# eggbotD1.net
KiCad netlist of a schematic drawn in EAGLE
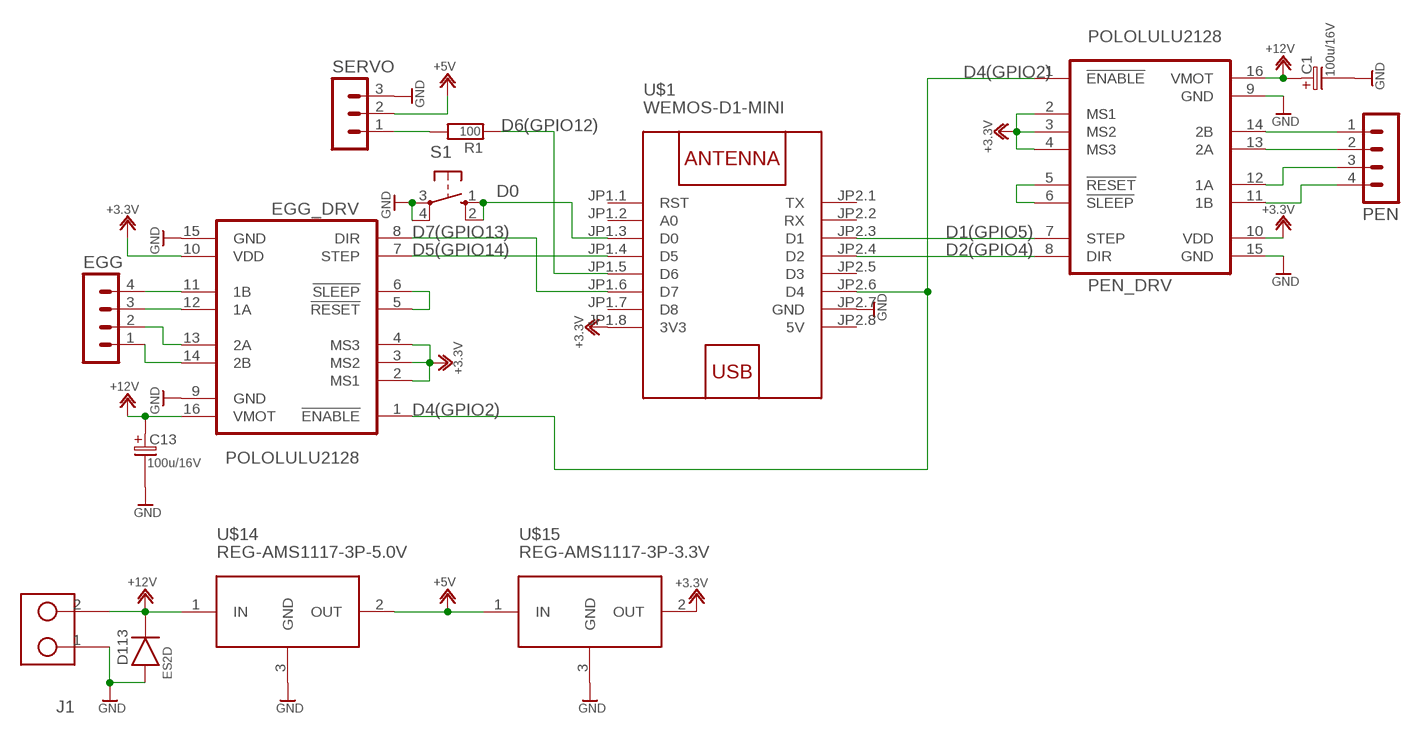
[diagram p0: schematic, sheet 1]

(export (version "E")
  (design (tool "Eeschema 10.0.6"))
  (components
    (comp (ref "C1")
      (value "100u/16V")
      (footprint "eagle-import:ES-3,5_8")
      (libsource (lib "eagle-import") (part "C-EL-3,5/8"))
    )
    (comp (ref "C13")
      (value "100u/16V")
      (footprint "eagle-import:ES-3,5_8")
      (libsource (lib "eagle-import") (part "C-EL-3,5/8"))
    )
    (comp (ref "D113")
      (value "ES2D")
      (footprint "eagle-import:SMB")
      (libsource (lib "eagle-import") (part "DIODESMB"))
    )
    (comp (ref "EGG")
      (value "MA04-1")
      (footprint "eagle-import:MA04-1")
      (libsource (lib "eagle-import") (part "MA04-1"))
    )
    (comp (ref "EGG_DRV")
      (value "POLOLULU2128")
      (footprint "eagle-import:POLOLULU2128")
      (libsource (lib "eagle-import") (part "POLOLULU2128"))
    )
    (comp (ref "J1")
      (value "GMKDS-2")
      (footprint "eagle-import:GMKDS1,5")
      (libsource (lib "eagle-import") (part "GMKDS-2"))
    )
    (comp (ref "PEN")
      (value "MA04-1")
      (footprint "eagle-import:MA04-1")
      (libsource (lib "eagle-import") (part "MA04-1"))
    )
    (comp (ref "PEN_DRV")
      (value "POLOLULU2128")
      (footprint "eagle-import:POLOLULU2128")
      (libsource (lib "eagle-import") (part "POLOLULU2128"))
    )
    (comp (ref "R1")
      (value "100")
      (footprint "eagle-import:0805")
      (libsource (lib "eagle-import") (part "RES-0805"))
    )
    (comp (ref "S1")
      (value "10-XX")
      (footprint "eagle-import:B3F-10XX")
      (fields (field (name "MPN") "B3F-1000"))
      (libsource (lib "eagle-import") (part "10-XX"))
    )
    (comp (ref "SERVO")
      (value "MA03-1")
      (footprint "eagle-import:MA03-1")
      (libsource (lib "eagle-import") (part "MA03-1"))
    )
    (comp (ref "U$1")
      (value "WEMOS-D1-MINI")
      (footprint "eagle-import:WEMOS-D1-MINI")
      (libsource (lib "eagle-import") (part "WEMOS-D1-MINI"))
    )
    (comp (ref "U$14")
      (value "REG-AMS1117-3P-5.0V")
      (footprint "eagle-import:REG-AMS1117-3P")
      (libsource (lib "eagle-import") (part "REG-AMS1117-3P-5.0V"))
    )
    (comp (ref "U$15")
      (value "REG-AMS1117-3P-3.3V")
      (footprint "eagle-import:REG-AMS1117-3P")
      (libsource (lib "eagle-import") (part "REG-AMS1117-3P-3.3V"))
    )
  )
  (nets
    (net (code "1") (name "+3.3V") (class "Default")
      (node (ref "EGG_DRV") (pin "10") (pinfunction "VDD_10") (pintype "power_in"))
      (node (ref "EGG_DRV") (pin "2") (pinfunction "MS1_2") (pintype "input"))
      (node (ref "EGG_DRV") (pin "3") (pinfunction "MS2_3") (pintype "input"))
      (node (ref "EGG_DRV") (pin "4") (pinfunction "MS3_4") (pintype "input"))
      (node (ref "PEN_DRV") (pin "10") (pinfunction "VDD_10") (pintype "power_in"))
      (node (ref "PEN_DRV") (pin "2") (pinfunction "MS1_2") (pintype "input"))
      (node (ref "PEN_DRV") (pin "3") (pinfunction "MS2_3") (pintype "input"))
      (node (ref "PEN_DRV") (pin "4") (pinfunction "MS3_4") (pintype "input"))
      (node (ref "U$1") (pin "JP1.8") (pinfunction "3V3_JP1.8") (pintype "power_in"))
      (node (ref "U$15") (pin "2") (pinfunction "OUT_2") (pintype "bidirectional"))
    )
    (net (code "2") (name "+5V") (class "Default")
      (node (ref "SERVO") (pin "2") (pinfunction "2_2") (pintype "passive"))
      (node (ref "U$14") (pin "2") (pinfunction "OUT_2") (pintype "bidirectional"))
      (node (ref "U$15") (pin "1") (pinfunction "IN_1") (pintype "bidirectional"))
    )
    (net (code "3") (name "+12V") (class "Default")
      (node (ref "C1") (pin "1") (pinfunction "1_1") (pintype "passive"))
      (node (ref "C13") (pin "1") (pinfunction "1_1") (pintype "passive"))
      (node (ref "D113") (pin "2") (pinfunction "K_2") (pintype "passive"))
      (node (ref "EGG_DRV") (pin "16") (pinfunction "VMOT_16") (pintype "power_in"))
      (node (ref "J1") (pin "2") (pinfunction "2_2") (pintype "passive"))
      (node (ref "PEN_DRV") (pin "16") (pinfunction "VMOT_16") (pintype "power_in"))
      (node (ref "U$14") (pin "1") (pinfunction "IN_1") (pintype "bidirectional"))
    )
    (net (code "4") (name "/5V") (class "Default")
      (node (ref "U$1") (pin "JP2.8") (pinfunction "5V_JP2.8") (pintype "power_in"))
    )
    (net (code "5") (name "/D0") (class "Default")
      (node (ref "S1") (pin "1") (pinfunction "S_1") (pintype "passive"))
      (node (ref "S1") (pin "2") (pinfunction "S1_2") (pintype "passive"))
      (node (ref "U$1") (pin "JP1.3") (pinfunction "D0_JP1.3") (pintype "bidirectional"))
    )
    (net (code "6") (name "/D1(GPIO5)") (class "Default")
      (node (ref "PEN_DRV") (pin "7") (pinfunction "STEP_7") (pintype "input"))
      (node (ref "U$1") (pin "JP2.3") (pinfunction "D1_JP2.3") (pintype "bidirectional"))
    )
    (net (code "7") (name "/D2(GPIO4)") (class "Default")
      (node (ref "PEN_DRV") (pin "8") (pinfunction "DIR_8") (pintype "input"))
      (node (ref "U$1") (pin "JP2.4") (pinfunction "D2_JP2.4") (pintype "bidirectional"))
    )
    (net (code "8") (name "/D4(GPIO2)") (class "Default")
      (node (ref "EGG_DRV") (pin "1") (pinfunction "~{ENABLE}_1") (pintype "input"))
      (node (ref "PEN_DRV") (pin "1") (pinfunction "~{ENABLE}_1") (pintype "input"))
      (node (ref "U$1") (pin "JP2.6") (pinfunction "D4_JP2.6") (pintype "bidirectional"))
    )
    (net (code "9") (name "/D5(GPIO14)") (class "Default")
      (node (ref "EGG_DRV") (pin "7") (pinfunction "STEP_7") (pintype "input"))
      (node (ref "U$1") (pin "JP1.4") (pinfunction "D5_JP1.4") (pintype "bidirectional"))
    )
    (net (code "10") (name "/D6(GPIO12)") (class "Default")
      (node (ref "R1") (pin "1") (pinfunction "1_1") (pintype "passive"))
      (node (ref "U$1") (pin "JP1.5") (pinfunction "D6_JP1.5") (pintype "bidirectional"))
    )
    (net (code "11") (name "/D7(GPIO13)") (class "Default")
      (node (ref "EGG_DRV") (pin "8") (pinfunction "DIR_8") (pintype "input"))
      (node (ref "U$1") (pin "JP1.6") (pinfunction "D7_JP1.6") (pintype "bidirectional"))
    )
    (net (code "12") (name "GND") (class "Default")
      (node (ref "C1") (pin "2") (pinfunction "2_2") (pintype "passive"))
      (node (ref "C13") (pin "2") (pinfunction "2_2") (pintype "passive"))
      (node (ref "D113") (pin "1") (pinfunction "A_1") (pintype "passive"))
      (node (ref "EGG_DRV") (pin "15") (pinfunction "GND_15") (pintype "power_in"))
      (node (ref "EGG_DRV") (pin "9") (pinfunction "GND_9") (pintype "power_in"))
      (node (ref "J1") (pin "1") (pinfunction "1_1") (pintype "passive"))
      (node (ref "PEN_DRV") (pin "15") (pinfunction "GND_15") (pintype "power_in"))
      (node (ref "PEN_DRV") (pin "9") (pinfunction "GND_9") (pintype "power_in"))
      (node (ref "S1") (pin "3") (pinfunction "P_3") (pintype "passive"))
      (node (ref "S1") (pin "4") (pinfunction "P1_4") (pintype "passive"))
      (node (ref "SERVO") (pin "3") (pinfunction "3_3") (pintype "passive"))
      (node (ref "U$1") (pin "JP2.7") (pinfunction "GND_JP2.7") (pintype "power_in"))
      (node (ref "U$14") (pin "3") (pinfunction "GND_3") (pintype "bidirectional"))
      (node (ref "U$15") (pin "3") (pinfunction "GND_3") (pintype "bidirectional"))
    )
    (net (code "13") (name "Net-(EGG_DRV-1A)") (class "Default")
      (node (ref "EGG") (pin "3") (pinfunction "3_3") (pintype "passive"))
      (node (ref "EGG_DRV") (pin "12") (pinfunction "1A_12") (pintype "output"))
    )
    (net (code "14") (name "Net-(EGG_DRV-1B)") (class "Default")
      (node (ref "EGG") (pin "4") (pinfunction "4_4") (pintype "passive"))
      (node (ref "EGG_DRV") (pin "11") (pinfunction "1B_11") (pintype "output"))
    )
    (net (code "15") (name "Net-(EGG_DRV-2A)") (class "Default")
      (node (ref "EGG") (pin "2") (pinfunction "2_2") (pintype "passive"))
      (node (ref "EGG_DRV") (pin "13") (pinfunction "2A_13") (pintype "output"))
    )
    (net (code "16") (name "Net-(EGG_DRV-2B)") (class "Default")
      (node (ref "EGG") (pin "1") (pinfunction "1_1") (pintype "passive"))
      (node (ref "EGG_DRV") (pin "14") (pinfunction "2B_14") (pintype "output"))
    )
    (net (code "17") (name "Net-(EGG_DRV-~{RESET})") (class "Default")
      (node (ref "EGG_DRV") (pin "5") (pinfunction "~{RESET}_5") (pintype "input"))
      (node (ref "EGG_DRV") (pin "6") (pinfunction "~{SLEEP}_6") (pintype "input"))
    )
    (net (code "18") (name "Net-(PEN_DRV-1A)") (class "Default")
      (node (ref "PEN") (pin "3") (pinfunction "3_3") (pintype "passive"))
      (node (ref "PEN_DRV") (pin "12") (pinfunction "1A_12") (pintype "output"))
    )
    (net (code "19") (name "Net-(PEN_DRV-1B)") (class "Default")
      (node (ref "PEN") (pin "4") (pinfunction "4_4") (pintype "passive"))
      (node (ref "PEN_DRV") (pin "11") (pinfunction "1B_11") (pintype "output"))
    )
    (net (code "20") (name "Net-(PEN_DRV-2A)") (class "Default")
      (node (ref "PEN") (pin "2") (pinfunction "2_2") (pintype "passive"))
      (node (ref "PEN_DRV") (pin "13") (pinfunction "2A_13") (pintype "output"))
    )
    (net (code "21") (name "Net-(PEN_DRV-2B)") (class "Default")
      (node (ref "PEN") (pin "1") (pinfunction "1_1") (pintype "passive"))
      (node (ref "PEN_DRV") (pin "14") (pinfunction "2B_14") (pintype "output"))
    )
    (net (code "22") (name "Net-(PEN_DRV-~{RESET})") (class "Default")
      (node (ref "PEN_DRV") (pin "5") (pinfunction "~{RESET}_5") (pintype "input"))
      (node (ref "PEN_DRV") (pin "6") (pinfunction "~{SLEEP}_6") (pintype "input"))
    )
    (net (code "23") (name "Net-(R1-Pad2)") (class "Default")
      (node (ref "R1") (pin "2") (pinfunction "2_2") (pintype "passive"))
      (node (ref "SERVO") (pin "1") (pinfunction "1_1") (pintype "passive"))
    )
    (net (code "24") (name "unconnected-(U$1-A0-PadJP1.2)") (class "Default")
      (node (ref "U$1") (pin "JP1.2") (pinfunction "A0_JP1.2") (pintype "bidirectional"))
    )
    (net (code "25") (name "unconnected-(U$1-D3-PadJP2.5)") (class "Default")
      (node (ref "U$1") (pin "JP2.5") (pinfunction "D3_JP2.5") (pintype "bidirectional"))
    )
    (net (code "26") (name "unconnected-(U$1-D8-PadJP1.7)") (class "Default")
      (node (ref "U$1") (pin "JP1.7") (pinfunction "D8_JP1.7") (pintype "bidirectional"))
    )
    (net (code "27") (name "unconnected-(U$1-RST-PadJP1.1)") (class "Default")
      (node (ref "U$1") (pin "JP1.1") (pinfunction "RST_JP1.1") (pintype "bidirectional"))
    )
    (net (code "28") (name "unconnected-(U$1-RX-PadJP2.2)") (class "Default")
      (node (ref "U$1") (pin "JP2.2") (pinfunction "RX_JP2.2") (pintype "bidirectional"))
    )
    (net (code "29") (name "unconnected-(U$1-TX-PadJP2.1)") (class "Default")
      (node (ref "U$1") (pin "JP2.1") (pinfunction "TX_JP2.1") (pintype "bidirectional"))
    )
  )
)
